# untitled.net
KiCad netlist of a schematic drawn in EAGLE
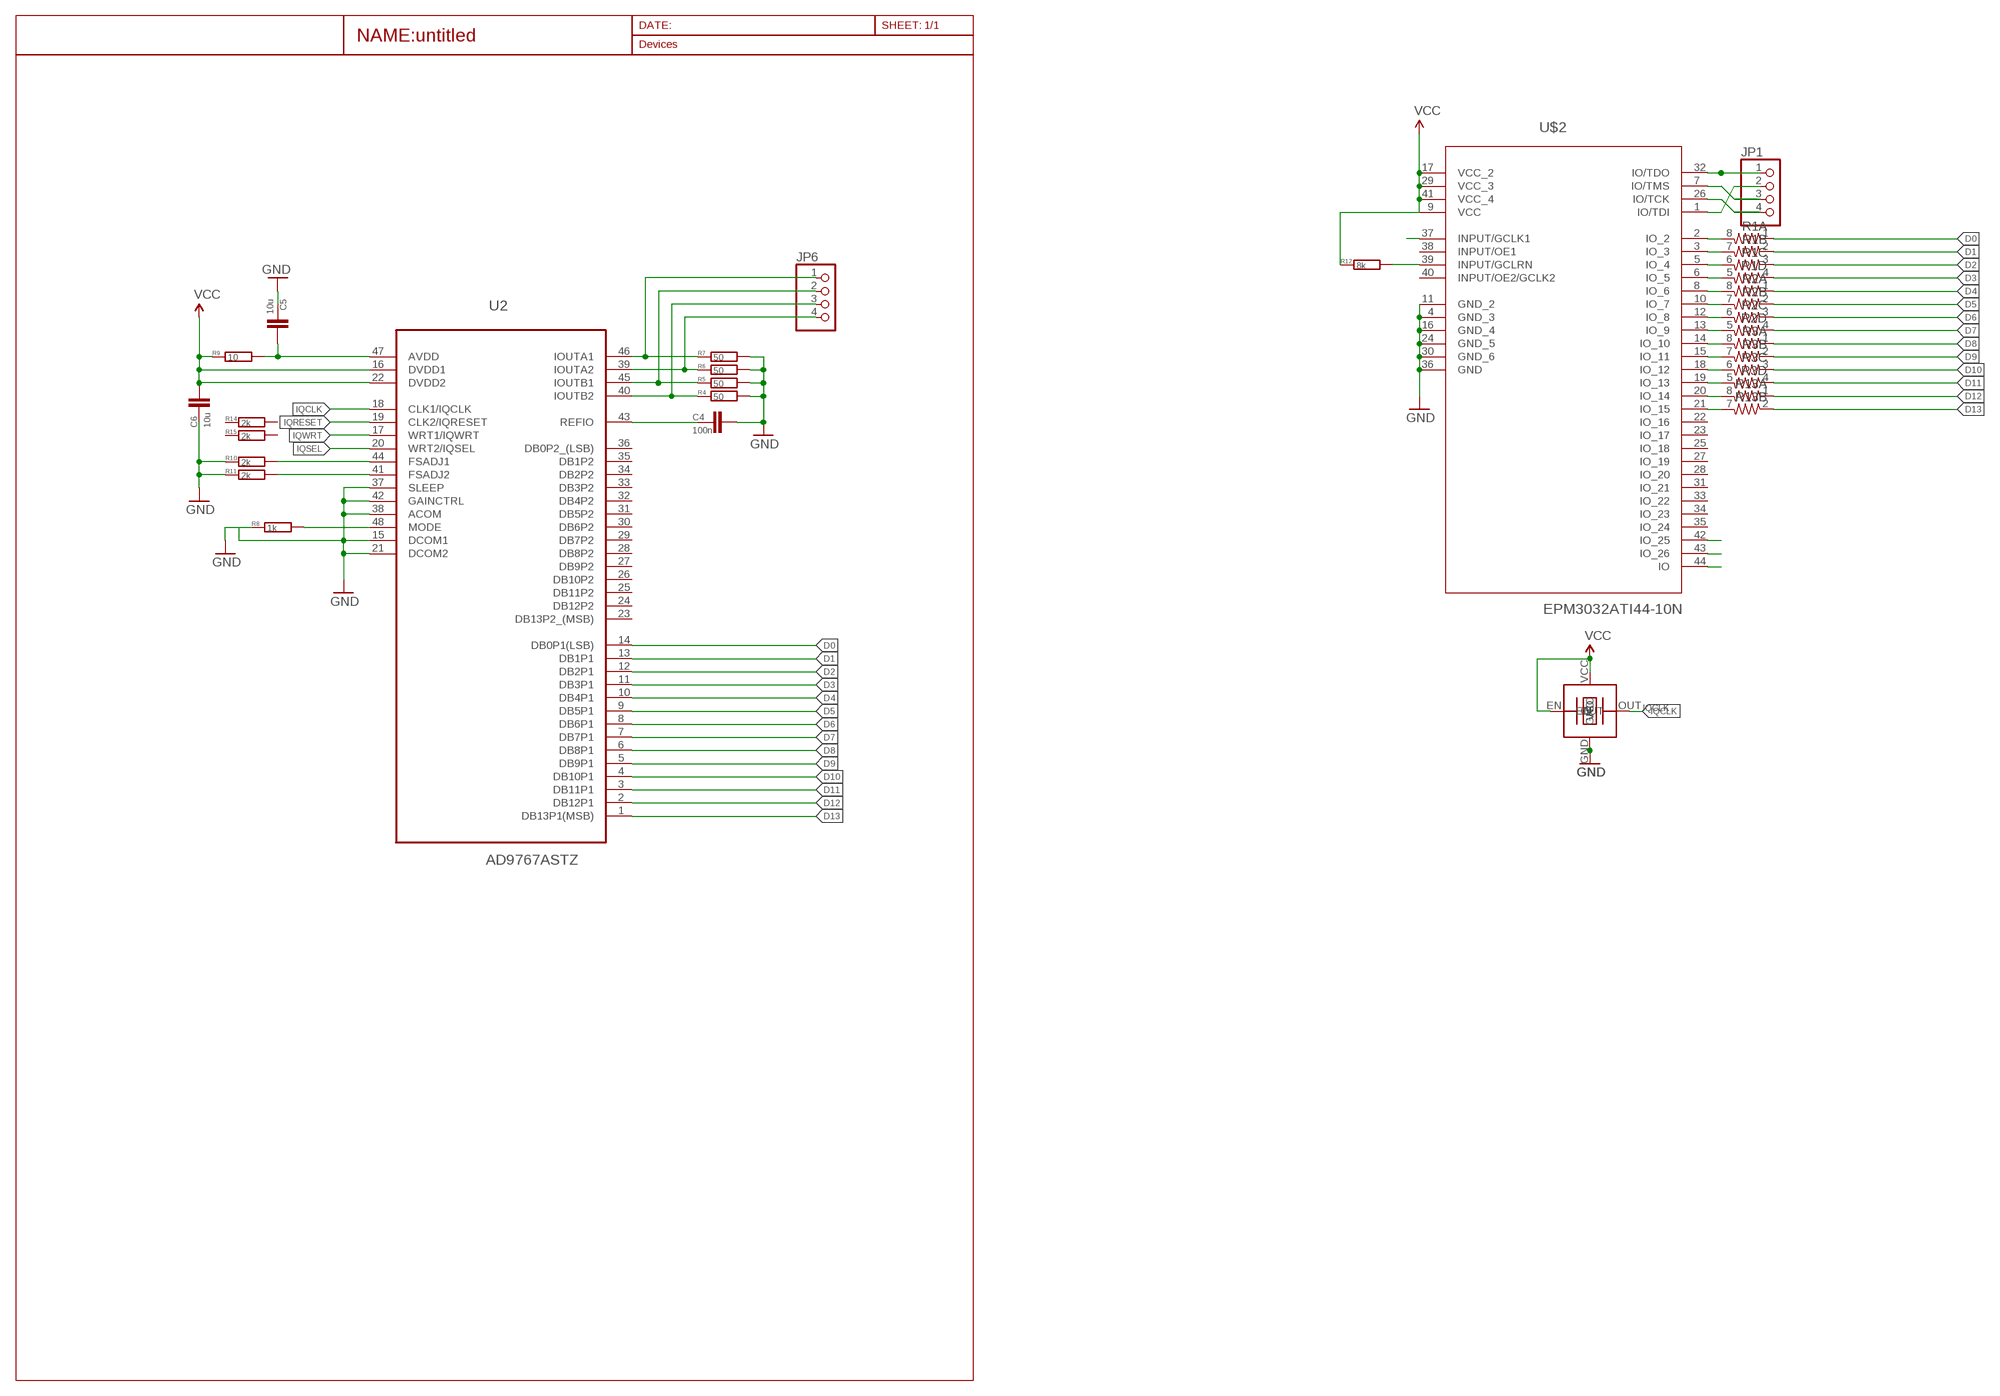
[diagram p0: schematic, sheet 1]

(export (version "E")
  (design (tool "Eeschema 10.0.6"))
  (components
    (comp (ref "C4")
      (value "100n")
      (footprint "eagle-import:C0805")
      (libsource (lib "eagle-import") (part "CC0805"))
    )
    (comp (ref "C5")
      (value "10u")
      (footprint "eagle-import:C0805")
      (libsource (lib "eagle-import") (part "CC0805"))
    )
    (comp (ref "C6")
      (value "10u")
      (footprint "eagle-import:C0805")
      (libsource (lib "eagle-import") (part "CC0805"))
    )
    (comp (ref "JP1")
      (value "PINHD-1X4")
      (footprint "eagle-import:1X04")
      (libsource (lib "eagle-import") (part "PINHD-1X4"))
    )
    (comp (ref "JP6")
      (value "PINHD-1X4")
      (footprint "eagle-import:1X04")
      (libsource (lib "eagle-import") (part "PINHD-1X4"))
    )
    (comp (ref "R1")
      (value "RESISTOR-ARRAY0603-ARV")
      (footprint "eagle-import:0603-ARV")
      (libsource (lib "eagle-import") (part "RESISTOR-ARRAY0603-ARV"))
    )
    (comp (ref "R2")
      (value "RESISTOR-ARRAY0603-ARV")
      (footprint "eagle-import:0603-ARV")
      (libsource (lib "eagle-import") (part "RESISTOR-ARRAY0603-ARV"))
    )
    (comp (ref "R3")
      (value "RESISTOR-ARRAY0603-ARV")
      (footprint "eagle-import:0603-ARV")
      (libsource (lib "eagle-import") (part "RESISTOR-ARRAY0603-ARV"))
    )
    (comp (ref "R4")
      (value "50")
      (footprint "eagle-import:R0805")
      (libsource (lib "eagle-import") (part "R0805"))
    )
    (comp (ref "R5")
      (value "50")
      (footprint "eagle-import:R0805")
      (libsource (lib "eagle-import") (part "R0805"))
    )
    (comp (ref "R6")
      (value "50")
      (footprint "eagle-import:R0805")
      (libsource (lib "eagle-import") (part "R0805"))
    )
    (comp (ref "R7")
      (value "50")
      (footprint "eagle-import:R0805")
      (libsource (lib "eagle-import") (part "R0805"))
    )
    (comp (ref "R8")
      (value "1k")
      (footprint "eagle-import:R0805")
      (libsource (lib "eagle-import") (part "R0805"))
    )
    (comp (ref "R9")
      (value "10")
      (footprint "eagle-import:R0805")
      (libsource (lib "eagle-import") (part "R0805"))
    )
    (comp (ref "R10")
      (value "2k")
      (footprint "eagle-import:R0805")
      (libsource (lib "eagle-import") (part "R0805"))
    )
    (comp (ref "R11")
      (value "2k")
      (footprint "eagle-import:R0805")
      (libsource (lib "eagle-import") (part "R0805"))
    )
    (comp (ref "R12")
      (value "8k")
      (footprint "eagle-import:R0805")
      (libsource (lib "eagle-import") (part "R0805"))
    )
    (comp (ref "R13")
      (value "RESISTOR-ARRAY0603-ARV")
      (footprint "eagle-import:0603-ARV")
      (libsource (lib "eagle-import") (part "RESISTOR-ARRAY0603-ARV"))
    )
    (comp (ref "R14")
      (value "2k")
      (footprint "eagle-import:R0805")
      (libsource (lib "eagle-import") (part "R0805"))
    )
    (comp (ref "R15")
      (value "2k")
      (footprint "eagle-import:R0805")
      (libsource (lib "eagle-import") (part "R0805"))
    )
    (comp (ref "U$2")
      (value "EPM3032ATI44-10N")
      (footprint "eagle-import:QFP80P1200X1200X120-44N")
      (libsource (lib "eagle-import") (part "EPM3032ATI44-10N"))
    )
    (comp (ref "U$3")
      (value "TXC-BA")
      (footprint "eagle-import:7X5")
      (libsource (lib "eagle-import") (part "TXC-BA"))
    )
    (comp (ref "U2")
      (value "AD9767ASTZ")
      (footprint "eagle-import:QFP50P900X900X160-48N")
      (libsource (lib "eagle-import") (part "AD9767ASTZ"))
    )
  )
  (nets
    (net (code "1") (name "D0") (class "Default")
      (node (ref "R1") (pin "1") (pinfunction "1_1") (pintype "passive"))
      (node (ref "U2") (pin "14") (pinfunction "DB0P1(LSB)_14") (pintype "bidirectional"))
    )
    (net (code "2") (name "D1") (class "Default")
      (node (ref "R1") (pin "2") (pinfunction "1_2") (pintype "passive"))
      (node (ref "U2") (pin "13") (pinfunction "DB1P1_13") (pintype "bidirectional"))
    )
    (net (code "3") (name "D2") (class "Default")
      (node (ref "R1") (pin "3") (pinfunction "1_3") (pintype "passive"))
      (node (ref "U2") (pin "12") (pinfunction "DB2P1_12") (pintype "bidirectional"))
    )
    (net (code "4") (name "D3") (class "Default")
      (node (ref "R1") (pin "4") (pinfunction "1_4") (pintype "passive"))
      (node (ref "U2") (pin "11") (pinfunction "DB3P1_11") (pintype "bidirectional"))
    )
    (net (code "5") (name "D4") (class "Default")
      (node (ref "R2") (pin "1") (pinfunction "1_1") (pintype "passive"))
      (node (ref "U2") (pin "10") (pinfunction "DB4P1_10") (pintype "bidirectional"))
    )
    (net (code "6") (name "D5") (class "Default")
      (node (ref "R2") (pin "2") (pinfunction "1_2") (pintype "passive"))
      (node (ref "U2") (pin "9") (pinfunction "DB5P1_9") (pintype "bidirectional"))
    )
    (net (code "7") (name "D6") (class "Default")
      (node (ref "R2") (pin "3") (pinfunction "1_3") (pintype "passive"))
      (node (ref "U2") (pin "8") (pinfunction "DB6P1_8") (pintype "bidirectional"))
    )
    (net (code "8") (name "D7") (class "Default")
      (node (ref "R2") (pin "4") (pinfunction "1_4") (pintype "passive"))
      (node (ref "U2") (pin "7") (pinfunction "DB7P1_7") (pintype "bidirectional"))
    )
    (net (code "9") (name "D8") (class "Default")
      (node (ref "R3") (pin "1") (pinfunction "1_1") (pintype "passive"))
      (node (ref "U2") (pin "6") (pinfunction "DB8P1_6") (pintype "bidirectional"))
    )
    (net (code "10") (name "D9") (class "Default")
      (node (ref "R3") (pin "2") (pinfunction "1_2") (pintype "passive"))
      (node (ref "U2") (pin "5") (pinfunction "DB9P1_5") (pintype "bidirectional"))
    )
    (net (code "11") (name "D10") (class "Default")
      (node (ref "R3") (pin "3") (pinfunction "1_3") (pintype "passive"))
      (node (ref "U2") (pin "4") (pinfunction "DB10P1_4") (pintype "bidirectional"))
    )
    (net (code "12") (name "D11") (class "Default")
      (node (ref "R3") (pin "4") (pinfunction "1_4") (pintype "passive"))
      (node (ref "U2") (pin "3") (pinfunction "DB11P1_3") (pintype "bidirectional"))
    )
    (net (code "13") (name "D12") (class "Default")
      (node (ref "R13") (pin "1") (pinfunction "1_1") (pintype "passive"))
      (node (ref "U2") (pin "2") (pinfunction "DB12P1_2") (pintype "bidirectional"))
    )
    (net (code "14") (name "D13") (class "Default")
      (node (ref "R13") (pin "2") (pinfunction "1_2") (pintype "passive"))
      (node (ref "U2") (pin "1") (pinfunction "DB13P1(MSB)_1") (pintype "bidirectional"))
    )
    (net (code "15") (name "GND") (class "Default")
      (node (ref "C4") (pin "1") (pinfunction "1_1") (pintype "passive"))
      (node (ref "C5") (pin "2") (pinfunction "2_2") (pintype "passive"))
      (node (ref "C6") (pin "2") (pinfunction "2_2") (pintype "passive"))
      (node (ref "R10") (pin "1") (pinfunction "1_1") (pintype "passive"))
      (node (ref "R11") (pin "1") (pinfunction "1_1") (pintype "passive"))
      (node (ref "R4") (pin "2") (pinfunction "2_2") (pintype "passive"))
      (node (ref "R5") (pin "2") (pinfunction "2_2") (pintype "passive"))
      (node (ref "R6") (pin "2") (pinfunction "2_2") (pintype "passive"))
      (node (ref "R7") (pin "2") (pinfunction "2_2") (pintype "passive"))
      (node (ref "R8") (pin "1") (pinfunction "1_1") (pintype "passive"))
      (node (ref "U$2") (pin "11") (pinfunction "GND_2_11") (pintype "passive"))
      (node (ref "U$2") (pin "16") (pinfunction "GND_4_16") (pintype "passive"))
      (node (ref "U$2") (pin "24") (pinfunction "GND_5_24") (pintype "passive"))
      (node (ref "U$2") (pin "30") (pinfunction "GND_6_30") (pintype "passive"))
      (node (ref "U$2") (pin "36") (pinfunction "GND_36") (pintype "passive"))
      (node (ref "U$2") (pin "4") (pinfunction "GND_3_4") (pintype "passive"))
      (node (ref "U$3") (pin "GND") (pinfunction "GND_GND") (pintype "bidirectional"))
      (node (ref "U2") (pin "15") (pinfunction "DCOM1_15") (pintype "passive"))
      (node (ref "U2") (pin "21") (pinfunction "DCOM2_21") (pintype "passive"))
      (node (ref "U2") (pin "37") (pinfunction "SLEEP_37") (pintype "passive"))
      (node (ref "U2") (pin "38") (pinfunction "ACOM_38") (pintype "passive"))
      (node (ref "U2") (pin "42") (pinfunction "GAINCTRL_42") (pintype "passive"))
    )
    (net (code "16") (name "IQCLK") (class "Default")
      (node (ref "U$2") (pin "37") (pinfunction "INPUT/GCLK1_37") (pintype "input"))
      (node (ref "U$3") (pin "OUT") (pinfunction "OUT_OUT") (pintype "bidirectional"))
      (node (ref "U2") (pin "18") (pinfunction "CLK1/IQCLK_18") (pintype "input"))
    )
    (net (code "17") (name "IQRESET") (class "Default")
      (node (ref "U$2") (pin "43") (pinfunction "IO_26_43") (pintype "bidirectional"))
      (node (ref "U2") (pin "19") (pinfunction "CLK2/IQRESET_19") (pintype "input"))
    )
    (net (code "18") (name "IQSEL") (class "Default")
      (node (ref "U$2") (pin "42") (pinfunction "IO_25_42") (pintype "bidirectional"))
      (node (ref "U2") (pin "20") (pinfunction "WRT2/IQSEL_20") (pintype "input"))
    )
    (net (code "19") (name "IQWRT") (class "Default")
      (node (ref "U$2") (pin "44") (pinfunction "IO_44") (pintype "bidirectional"))
      (node (ref "U2") (pin "17") (pinfunction "WRT1/IQWRT_17") (pintype "input"))
    )
    (net (code "20") (name "Net-(R1A-2)") (class "Default")
      (node (ref "R1") (pin "8") (pinfunction "2_8") (pintype "passive"))
      (node (ref "U$2") (pin "2") (pinfunction "IO_2_2") (pintype "bidirectional"))
    )
    (net (code "21") (name "Net-(R1B-2)") (class "Default")
      (node (ref "R1") (pin "7") (pinfunction "2_7") (pintype "passive"))
      (node (ref "U$2") (pin "3") (pinfunction "IO_3_3") (pintype "bidirectional"))
    )
    (net (code "22") (name "Net-(R1C-2)") (class "Default")
      (node (ref "R1") (pin "6") (pinfunction "2_6") (pintype "passive"))
      (node (ref "U$2") (pin "5") (pinfunction "IO_4_5") (pintype "bidirectional"))
    )
    (net (code "23") (name "Net-(R1D-2)") (class "Default")
      (node (ref "R1") (pin "5") (pinfunction "2_5") (pintype "passive"))
      (node (ref "U$2") (pin "6") (pinfunction "IO_5_6") (pintype "bidirectional"))
    )
    (net (code "24") (name "Net-(R2A-2)") (class "Default")
      (node (ref "R2") (pin "8") (pinfunction "2_8") (pintype "passive"))
      (node (ref "U$2") (pin "8") (pinfunction "IO_6_8") (pintype "bidirectional"))
    )
    (net (code "25") (name "Net-(R2B-2)") (class "Default")
      (node (ref "R2") (pin "7") (pinfunction "2_7") (pintype "passive"))
      (node (ref "U$2") (pin "10") (pinfunction "IO_7_10") (pintype "bidirectional"))
    )
    (net (code "26") (name "Net-(R2C-2)") (class "Default")
      (node (ref "R2") (pin "6") (pinfunction "2_6") (pintype "passive"))
      (node (ref "U$2") (pin "12") (pinfunction "IO_8_12") (pintype "bidirectional"))
    )
    (net (code "27") (name "Net-(R2D-2)") (class "Default")
      (node (ref "R2") (pin "5") (pinfunction "2_5") (pintype "passive"))
      (node (ref "U$2") (pin "13") (pinfunction "IO_9_13") (pintype "bidirectional"))
    )
    (net (code "28") (name "Net-(R3A-2)") (class "Default")
      (node (ref "R3") (pin "8") (pinfunction "2_8") (pintype "passive"))
      (node (ref "U$2") (pin "14") (pinfunction "IO_10_14") (pintype "bidirectional"))
    )
    (net (code "29") (name "Net-(R3B-2)") (class "Default")
      (node (ref "R3") (pin "7") (pinfunction "2_7") (pintype "passive"))
      (node (ref "U$2") (pin "15") (pinfunction "IO_11_15") (pintype "bidirectional"))
    )
    (net (code "30") (name "Net-(R3C-2)") (class "Default")
      (node (ref "R3") (pin "6") (pinfunction "2_6") (pintype "passive"))
      (node (ref "U$2") (pin "18") (pinfunction "IO_12_18") (pintype "bidirectional"))
    )
    (net (code "31") (name "Net-(R3D-2)") (class "Default")
      (node (ref "R3") (pin "5") (pinfunction "2_5") (pintype "passive"))
      (node (ref "U$2") (pin "19") (pinfunction "IO_13_19") (pintype "bidirectional"))
    )
    (net (code "32") (name "Net-(R13A-2)") (class "Default")
      (node (ref "R13") (pin "8") (pinfunction "2_8") (pintype "passive"))
      (node (ref "U$2") (pin "20") (pinfunction "IO_14_20") (pintype "bidirectional"))
    )
    (net (code "33") (name "Net-(R13B-2)") (class "Default")
      (node (ref "R13") (pin "7") (pinfunction "2_7") (pintype "passive"))
      (node (ref "U$2") (pin "21") (pinfunction "IO_15_21") (pintype "bidirectional"))
    )
    (net (code "34") (name "Net-(U$2-INPUT{slash}GCLRN)") (class "Default")
      (node (ref "R12") (pin "2") (pinfunction "2_2") (pintype "passive"))
      (node (ref "U$2") (pin "39") (pinfunction "INPUT/GCLRN_39") (pintype "input"))
    )
    (net (code "35") (name "Net-(U$2-IO{slash}TCK)") (class "Default")
      (node (ref "JP1") (pin "4") (pinfunction "4_4") (pintype "passive"))
      (node (ref "U$2") (pin "26") (pinfunction "IO/TCK_26") (pintype "bidirectional"))
    )
    (net (code "36") (name "Net-(U$2-IO{slash}TDI)") (class "Default")
      (node (ref "JP1") (pin "2") (pinfunction "2_2") (pintype "passive"))
      (node (ref "U$2") (pin "1") (pinfunction "IO/TDI_1") (pintype "bidirectional"))
    )
    (net (code "37") (name "Net-(U$2-IO{slash}TDO)") (class "Default")
      (node (ref "JP1") (pin "1") (pinfunction "1_1") (pintype "passive"))
      (node (ref "U$2") (pin "32") (pinfunction "IO/TDO_32") (pintype "bidirectional"))
    )
    (net (code "38") (name "Net-(U$2-IO{slash}TMS)") (class "Default")
      (node (ref "JP1") (pin "3") (pinfunction "3_3") (pintype "passive"))
      (node (ref "U$2") (pin "7") (pinfunction "IO/TMS_7") (pintype "bidirectional"))
    )
    (net (code "39") (name "Net-(U2-AVDD)") (class "Default")
      (node (ref "C5") (pin "1") (pinfunction "1_1") (pintype "passive"))
      (node (ref "R9") (pin "2") (pinfunction "2_2") (pintype "passive"))
      (node (ref "U2") (pin "47") (pinfunction "AVDD_47") (pintype "power_in"))
    )
    (net (code "40") (name "Net-(U2-FSADJ1)") (class "Default")
      (node (ref "R10") (pin "2") (pinfunction "2_2") (pintype "passive"))
      (node (ref "U2") (pin "44") (pinfunction "FSADJ1_44") (pintype "passive"))
    )
    (net (code "41") (name "Net-(U2-FSADJ2)") (class "Default")
      (node (ref "R11") (pin "2") (pinfunction "2_2") (pintype "passive"))
      (node (ref "U2") (pin "41") (pinfunction "FSADJ2_41") (pintype "passive"))
    )
    (net (code "42") (name "Net-(U2-IOUTA1)") (class "Default")
      (node (ref "JP6") (pin "1") (pinfunction "1_1") (pintype "passive"))
      (node (ref "R7") (pin "1") (pinfunction "1_1") (pintype "passive"))
      (node (ref "U2") (pin "46") (pinfunction "IOUTA1_46") (pintype "output"))
    )
    (net (code "43") (name "Net-(U2-IOUTA2)") (class "Default")
      (node (ref "JP6") (pin "4") (pinfunction "4_4") (pintype "passive"))
      (node (ref "R6") (pin "1") (pinfunction "1_1") (pintype "passive"))
      (node (ref "U2") (pin "39") (pinfunction "IOUTA2_39") (pintype "output"))
    )
    (net (code "44") (name "Net-(U2-IOUTB1)") (class "Default")
      (node (ref "JP6") (pin "2") (pinfunction "2_2") (pintype "passive"))
      (node (ref "R5") (pin "1") (pinfunction "1_1") (pintype "passive"))
      (node (ref "U2") (pin "45") (pinfunction "IOUTB1_45") (pintype "output"))
    )
    (net (code "45") (name "Net-(U2-IOUTB2)") (class "Default")
      (node (ref "JP6") (pin "3") (pinfunction "3_3") (pintype "passive"))
      (node (ref "R4") (pin "1") (pinfunction "1_1") (pintype "passive"))
      (node (ref "U2") (pin "40") (pinfunction "IOUTB2_40") (pintype "output"))
    )
    (net (code "46") (name "Net-(U2-MODE)") (class "Default")
      (node (ref "R8") (pin "2") (pinfunction "2_2") (pintype "passive"))
      (node (ref "U2") (pin "48") (pinfunction "MODE_48") (pintype "passive"))
    )
    (net (code "47") (name "Net-(U2-REFIO)") (class "Default")
      (node (ref "C4") (pin "2") (pinfunction "2_2") (pintype "passive"))
      (node (ref "U2") (pin "43") (pinfunction "REFIO_43") (pintype "bidirectional"))
    )
    (net (code "48") (name "VCC") (class "Default")
      (node (ref "C6") (pin "1") (pinfunction "1_1") (pintype "passive"))
      (node (ref "R12") (pin "1") (pinfunction "1_1") (pintype "passive"))
      (node (ref "R9") (pin "1") (pinfunction "1_1") (pintype "passive"))
      (node (ref "U$2") (pin "17") (pinfunction "VCC_2_17") (pintype "power_in"))
      (node (ref "U$2") (pin "29") (pinfunction "VCC_3_29") (pintype "power_in"))
      (node (ref "U$2") (pin "41") (pinfunction "VCC_4_41") (pintype "power_in"))
      (node (ref "U$2") (pin "9") (pinfunction "VCC_9") (pintype "power_in"))
      (node (ref "U$3") (pin "EN") (pinfunction "EN_EN") (pintype "bidirectional"))
      (node (ref "U$3") (pin "VCC") (pinfunction "VCC_VCC") (pintype "bidirectional"))
      (node (ref "U2") (pin "16") (pinfunction "DVDD1_16") (pintype "power_in"))
      (node (ref "U2") (pin "22") (pinfunction "DVDD2_22") (pintype "power_in"))
    )
    (net (code "49") (name "unconnected-(R14-Pad1)") (class "Default")
      (node (ref "R14") (pin "1") (pinfunction "1_1") (pintype "passive"))
    )
    (net (code "50") (name "unconnected-(R14-Pad2)") (class "Default")
      (node (ref "R14") (pin "2") (pinfunction "2_2") (pintype "passive"))
    )
    (net (code "51") (name "unconnected-(R15-Pad1)") (class "Default")
      (node (ref "R15") (pin "1") (pinfunction "1_1") (pintype "passive"))
    )
    (net (code "52") (name "unconnected-(R15-Pad2)") (class "Default")
      (node (ref "R15") (pin "2") (pinfunction "2_2") (pintype "passive"))
    )
    (net (code "53") (name "unconnected-(U$2-INPUT{slash}OE1-Pad38)") (class "Default")
      (node (ref "U$2") (pin "38") (pinfunction "INPUT/OE1_38") (pintype "input"))
    )
    (net (code "54") (name "unconnected-(U$2-INPUT{slash}OE2{slash}GCLK2-Pad40)") (class "Default")
      (node (ref "U$2") (pin "40") (pinfunction "INPUT/OE2/GCLK2_40") (pintype "input"))
    )
    (net (code "55") (name "unconnected-(U$2-IO_16-Pad22)") (class "Default")
      (node (ref "U$2") (pin "22") (pinfunction "IO_16_22") (pintype "bidirectional"))
    )
    (net (code "56") (name "unconnected-(U$2-IO_17-Pad23)") (class "Default")
      (node (ref "U$2") (pin "23") (pinfunction "IO_17_23") (pintype "bidirectional"))
    )
    (net (code "57") (name "unconnected-(U$2-IO_18-Pad25)") (class "Default")
      (node (ref "U$2") (pin "25") (pinfunction "IO_18_25") (pintype "bidirectional"))
    )
    (net (code "58") (name "unconnected-(U$2-IO_19-Pad27)") (class "Default")
      (node (ref "U$2") (pin "27") (pinfunction "IO_19_27") (pintype "bidirectional"))
    )
    (net (code "59") (name "unconnected-(U$2-IO_20-Pad28)") (class "Default")
      (node (ref "U$2") (pin "28") (pinfunction "IO_20_28") (pintype "bidirectional"))
    )
    (net (code "60") (name "unconnected-(U$2-IO_21-Pad31)") (class "Default")
      (node (ref "U$2") (pin "31") (pinfunction "IO_21_31") (pintype "bidirectional"))
    )
    (net (code "61") (name "unconnected-(U$2-IO_22-Pad33)") (class "Default")
      (node (ref "U$2") (pin "33") (pinfunction "IO_22_33") (pintype "bidirectional"))
    )
    (net (code "62") (name "unconnected-(U$2-IO_23-Pad34)") (class "Default")
      (node (ref "U$2") (pin "34") (pinfunction "IO_23_34") (pintype "bidirectional"))
    )
    (net (code "63") (name "unconnected-(U$2-IO_24-Pad35)") (class "Default")
      (node (ref "U$2") (pin "35") (pinfunction "IO_24_35") (pintype "bidirectional"))
    )
    (net (code "64") (name "unconnected-(U2-DB0P2_(LSB)-Pad36)") (class "Default")
      (node (ref "U2") (pin "36") (pinfunction "DB0P2_(LSB)_36") (pintype "bidirectional"))
    )
    (net (code "65") (name "unconnected-(U2-DB1P2-Pad35)") (class "Default")
      (node (ref "U2") (pin "35") (pinfunction "DB1P2_35") (pintype "bidirectional"))
    )
    (net (code "66") (name "unconnected-(U2-DB2P2-Pad34)") (class "Default")
      (node (ref "U2") (pin "34") (pinfunction "DB2P2_34") (pintype "bidirectional"))
    )
    (net (code "67") (name "unconnected-(U2-DB3P2-Pad33)") (class "Default")
      (node (ref "U2") (pin "33") (pinfunction "DB3P2_33") (pintype "bidirectional"))
    )
    (net (code "68") (name "unconnected-(U2-DB4P2-Pad32)") (class "Default")
      (node (ref "U2") (pin "32") (pinfunction "DB4P2_32") (pintype "bidirectional"))
    )
    (net (code "69") (name "unconnected-(U2-DB5P2-Pad31)") (class "Default")
      (node (ref "U2") (pin "31") (pinfunction "DB5P2_31") (pintype "bidirectional"))
    )
    (net (code "70") (name "unconnected-(U2-DB6P2-Pad30)") (class "Default")
      (node (ref "U2") (pin "30") (pinfunction "DB6P2_30") (pintype "bidirectional"))
    )
    (net (code "71") (name "unconnected-(U2-DB7P2-Pad29)") (class "Default")
      (node (ref "U2") (pin "29") (pinfunction "DB7P2_29") (pintype "bidirectional"))
    )
    (net (code "72") (name "unconnected-(U2-DB8P2-Pad28)") (class "Default")
      (node (ref "U2") (pin "28") (pinfunction "DB8P2_28") (pintype "bidirectional"))
    )
    (net (code "73") (name "unconnected-(U2-DB9P2-Pad27)") (class "Default")
      (node (ref "U2") (pin "27") (pinfunction "DB9P2_27") (pintype "bidirectional"))
    )
    (net (code "74") (name "unconnected-(U2-DB10P2-Pad26)") (class "Default")
      (node (ref "U2") (pin "26") (pinfunction "DB10P2_26") (pintype "bidirectional"))
    )
    (net (code "75") (name "unconnected-(U2-DB11P2-Pad25)") (class "Default")
      (node (ref "U2") (pin "25") (pinfunction "DB11P2_25") (pintype "bidirectional"))
    )
    (net (code "76") (name "unconnected-(U2-DB12P2-Pad24)") (class "Default")
      (node (ref "U2") (pin "24") (pinfunction "DB12P2_24") (pintype "bidirectional"))
    )
    (net (code "77") (name "unconnected-(U2-DB13P2_(MSB)-Pad23)") (class "Default")
      (node (ref "U2") (pin "23") (pinfunction "DB13P2_(MSB)_23") (pintype "bidirectional"))
    )
  )
)
